# IMU_Board.net
KiCad netlist of a schematic drawn in EAGLE
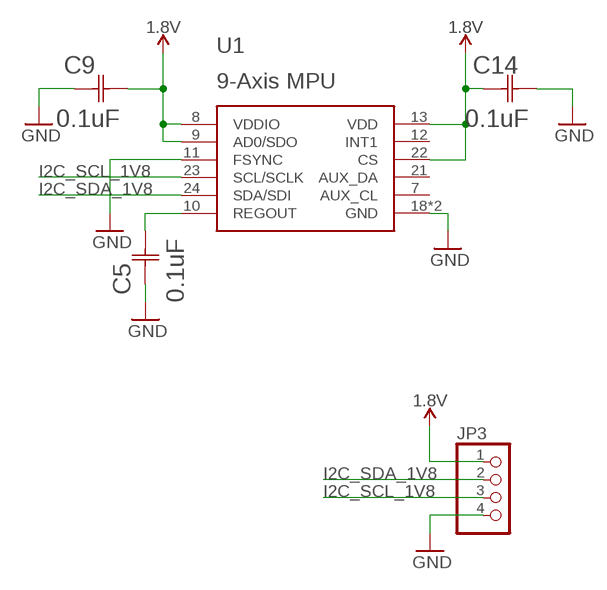
[diagram p0: schematic, sheet 1]

(export (version "E")
  (design (tool "Eeschema 10.0.6"))
  (components
    (comp (ref "C5")
      (value "0.1uF")
      (footprint "eagle-import:0805")
      (fields
        (field (name "MANUFACTURER_PART_NUMBER") "08055C104KAT2A")
        (field (name "COPYRIGHT") "Copyright C 2015 Accelerated Designs. All rights reserved")
      )
      (libsource (lib "eagle-import") (part "08055C104KAT2A"))
    )
    (comp (ref "C9")
      (value "0.1uF")
      (footprint "eagle-import:0805")
      (fields
        (field (name "MANUFACTURER_PART_NUMBER") "08055C104KAT2A")
        (field (name "COPYRIGHT") "Copyright C 2015 Accelerated Designs. All rights reserved")
      )
      (libsource (lib "eagle-import") (part "08055C104KAT2A"))
    )
    (comp (ref "C14")
      (value "0.1uF")
      (footprint "eagle-import:0805")
      (fields
        (field (name "MANUFACTURER_PART_NUMBER") "08055C104KAT2A")
        (field (name "COPYRIGHT") "Copyright C 2015 Accelerated Designs. All rights reserved")
      )
      (libsource (lib "eagle-import") (part "08055C104KAT2A"))
    )
    (comp (ref "JP3")
      (value "PINHD-1X4")
      (footprint "eagle-import:1X04")
      (libsource (lib "eagle-import") (part "PINHD-1X4"))
    )
    (comp (ref "U1")
      (value "ICM-20948")
      (footprint "eagle-import:QFN40P300X300X105-25N")
      (libsource (lib "eagle-import") (part "ICM-20948"))
    )
  )
  (nets
    (net (code "1") (name "/I2C_SCL_1V8") (class "Default")
      (node (ref "JP3") (pin "3") (pinfunction "3_3") (pintype "passive"))
      (node (ref "U1") (pin "23") (pinfunction "SCL/SCLK_23") (pintype "bidirectional"))
    )
    (net (code "2") (name "/I2C_SDA_1V8") (class "Default")
      (node (ref "JP3") (pin "2") (pinfunction "2_2") (pintype "passive"))
      (node (ref "U1") (pin "24") (pinfunction "SDA/SDI_24") (pintype "bidirectional"))
    )
    (net (code "3") (name "1.8V") (class "Default")
      (node (ref "C14") (pin "1") (pinfunction "1_1") (pintype "passive"))
      (node (ref "C9") (pin "2") (pinfunction "2_2") (pintype "passive"))
      (node (ref "JP3") (pin "1") (pinfunction "1_1") (pintype "passive"))
      (node (ref "U1") (pin "13") (pinfunction "VDD_13") (pintype "bidirectional"))
      (node (ref "U1") (pin "22") (pinfunction "CS_22") (pintype "bidirectional"))
      (node (ref "U1") (pin "8") (pinfunction "VDDIO_8") (pintype "bidirectional"))
      (node (ref "U1") (pin "9") (pinfunction "AD0/SDO_9") (pintype "bidirectional"))
    )
    (net (code "4") (name "GND") (class "Default")
      (node (ref "C14") (pin "2") (pinfunction "2_2") (pintype "passive"))
      (node (ref "C5") (pin "1") (pinfunction "1_1") (pintype "passive"))
      (node (ref "C9") (pin "1") (pinfunction "1_1") (pintype "passive"))
      (node (ref "JP3") (pin "4") (pinfunction "4_4") (pintype "passive"))
      (node (ref "U1") (pin "11") (pinfunction "FSYNC_11") (pintype "bidirectional"))
      (node (ref "U1") (pin "18") (pinfunction "GND_18") (pintype "bidirectional"))
      (node (ref "U1") (pin "20") (pinfunction "GND_20") (pintype "bidirectional"))
    )
    (net (code "5") (name "Net-(U1-REGOUT)") (class "Default")
      (node (ref "C5") (pin "2") (pinfunction "2_2") (pintype "passive"))
      (node (ref "U1") (pin "10") (pinfunction "REGOUT_10") (pintype "bidirectional"))
    )
    (net (code "6") (name "unconnected-(U1-AUX_CL-Pad7)") (class "Default")
      (node (ref "U1") (pin "7") (pinfunction "AUX_CL_7") (pintype "bidirectional"))
    )
    (net (code "7") (name "unconnected-(U1-AUX_DA-Pad21)") (class "Default")
      (node (ref "U1") (pin "21") (pinfunction "AUX_DA_21") (pintype "bidirectional"))
    )
    (net (code "8") (name "unconnected-(U1-INT1-Pad12)") (class "Default")
      (node (ref "U1") (pin "12") (pinfunction "INT1_12") (pintype "bidirectional"))
    )
  )
)
